# M304B.net
KiCad netlist of a schematic drawn in EAGLE
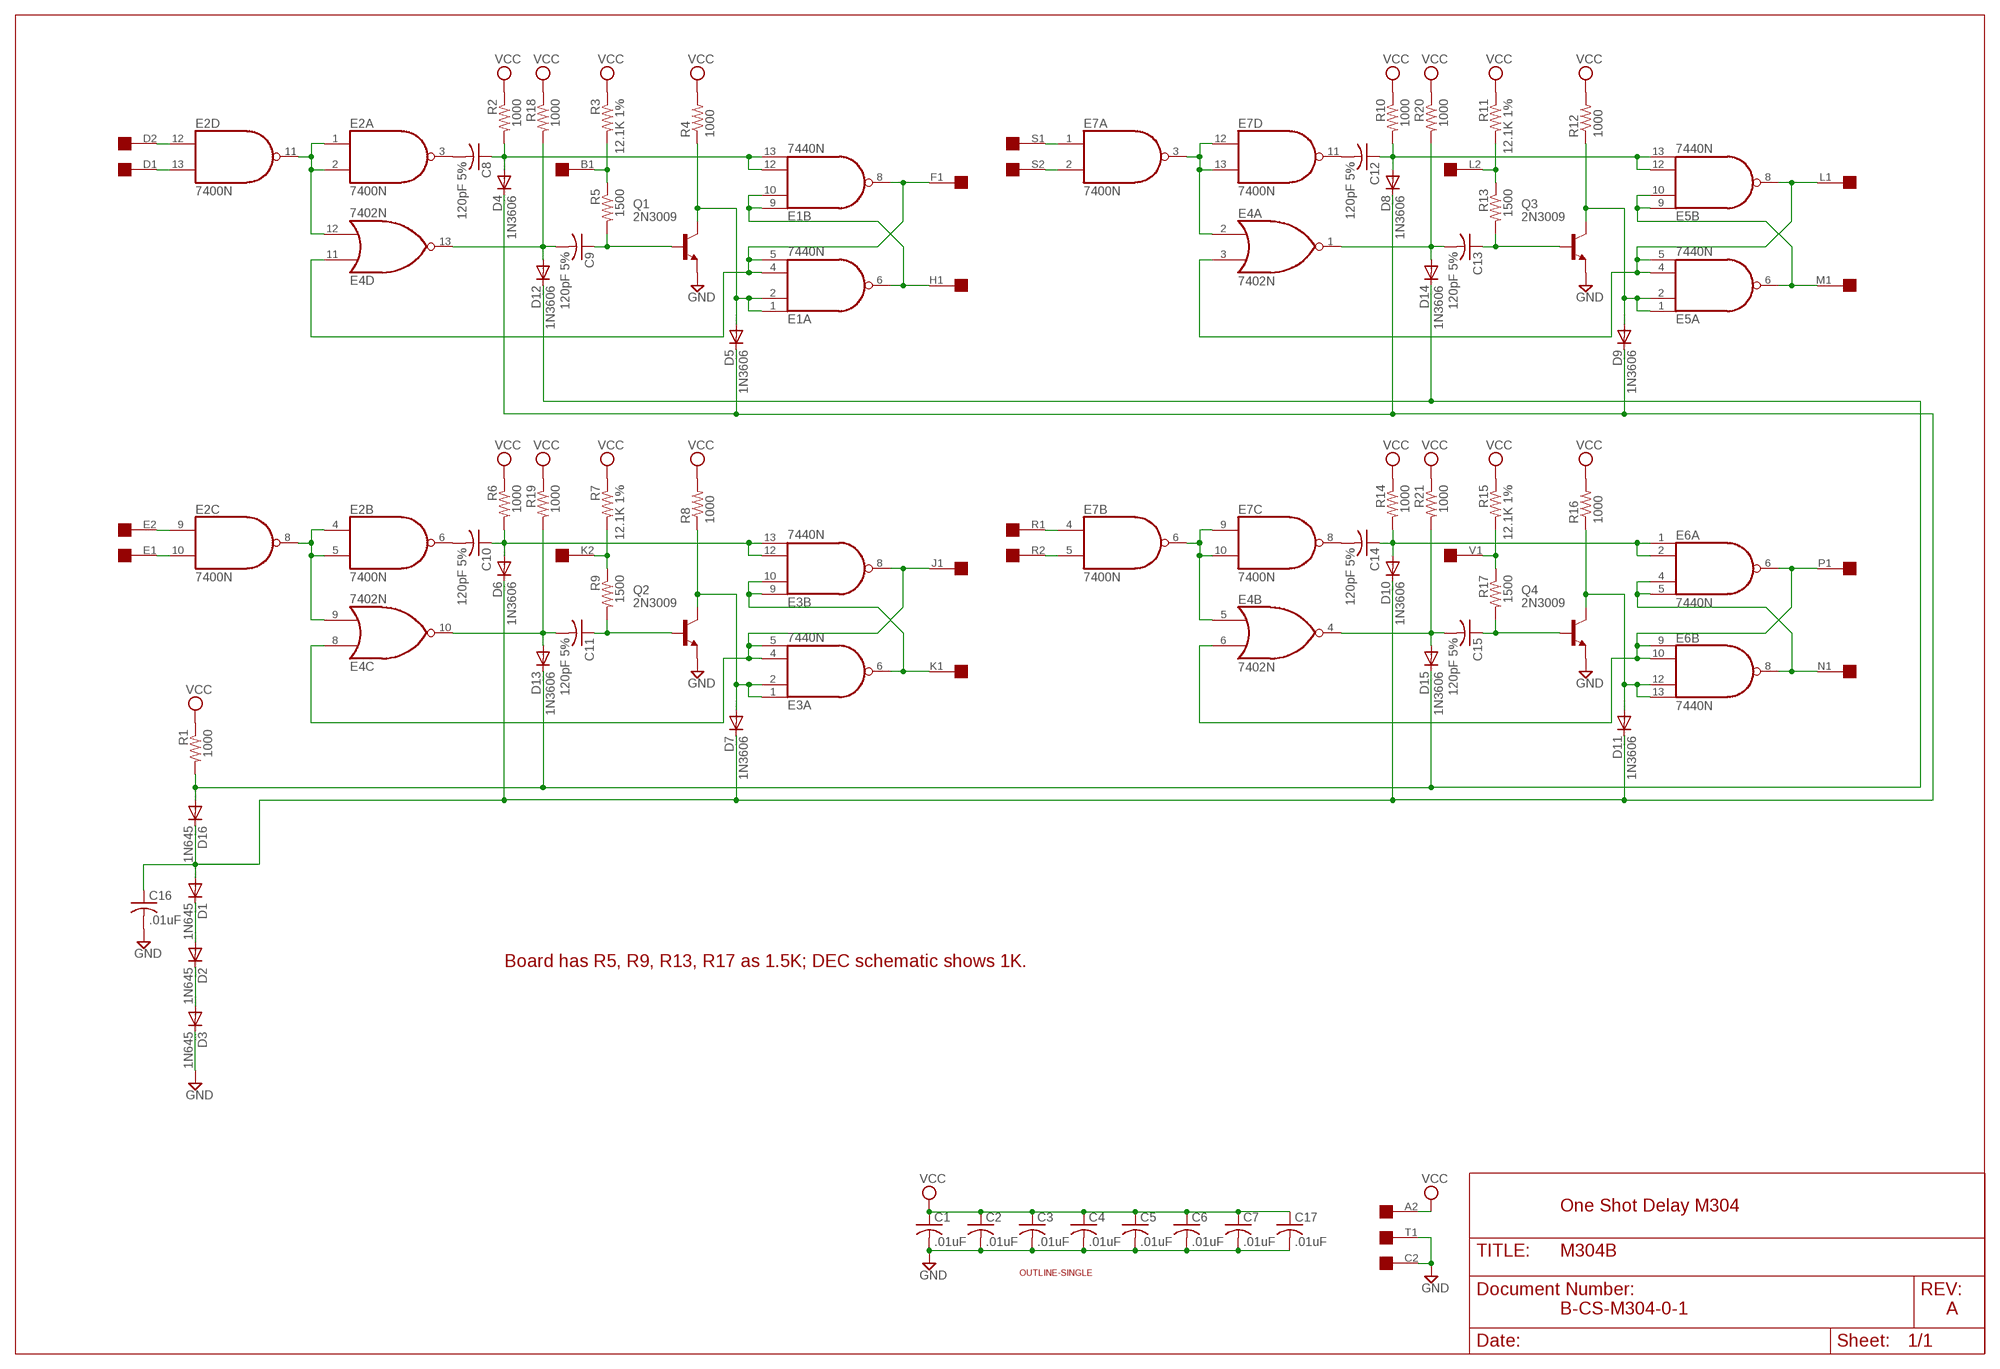
[diagram p0: schematic, sheet 1]

(export (version "E")
  (design (tool "Eeschema 10.0.6"))
  (components
    (comp (ref "C1")
      (value ".01uF")
      (footprint "eagle-import:C050-025X075")
      (libsource (lib "eagle-import") (part "C-US050-025X075"))
    )
    (comp (ref "C2")
      (value ".01uF")
      (footprint "eagle-import:C050-025X075")
      (libsource (lib "eagle-import") (part "C-US050-025X075"))
    )
    (comp (ref "C3")
      (value ".01uF")
      (footprint "eagle-import:C050-025X075")
      (libsource (lib "eagle-import") (part "C-US050-025X075"))
    )
    (comp (ref "C4")
      (value ".01uF")
      (footprint "eagle-import:C050-025X075")
      (libsource (lib "eagle-import") (part "C-US050-025X075"))
    )
    (comp (ref "C5")
      (value ".01uF")
      (footprint "eagle-import:C050-025X075")
      (libsource (lib "eagle-import") (part "C-US050-025X075"))
    )
    (comp (ref "C6")
      (value ".01uF")
      (footprint "eagle-import:C050-025X075")
      (libsource (lib "eagle-import") (part "C-US050-025X075"))
    )
    (comp (ref "C7")
      (value ".01uF")
      (footprint "eagle-import:C050-025X075")
      (libsource (lib "eagle-import") (part "C-US050-025X075"))
    )
    (comp (ref "C8")
      (value "120pF 5%")
      (footprint "eagle-import:C050-025X075")
      (libsource (lib "eagle-import") (part "C-US050-025X075"))
    )
    (comp (ref "C9")
      (value "120pF 5%")
      (footprint "eagle-import:C050-025X075")
      (libsource (lib "eagle-import") (part "C-US050-025X075"))
    )
    (comp (ref "C10")
      (value "120pF 5%")
      (footprint "eagle-import:C050-025X075")
      (libsource (lib "eagle-import") (part "C-US050-025X075"))
    )
    (comp (ref "C11")
      (value "120pF 5%")
      (footprint "eagle-import:C050-025X075")
      (libsource (lib "eagle-import") (part "C-US050-025X075"))
    )
    (comp (ref "C12")
      (value "120pF 5%")
      (footprint "eagle-import:C050-025X075")
      (libsource (lib "eagle-import") (part "C-US050-025X075"))
    )
    (comp (ref "C13")
      (value "120pF 5%")
      (footprint "eagle-import:C050-025X075")
      (libsource (lib "eagle-import") (part "C-US050-025X075"))
    )
    (comp (ref "C14")
      (value "120pF 5%")
      (footprint "eagle-import:C050-025X075")
      (libsource (lib "eagle-import") (part "C-US050-025X075"))
    )
    (comp (ref "C15")
      (value "120pF 5%")
      (footprint "eagle-import:C050-025X075")
      (libsource (lib "eagle-import") (part "C-US050-025X075"))
    )
    (comp (ref "C16")
      (value ".01uF")
      (footprint "eagle-import:C050-025X075")
      (libsource (lib "eagle-import") (part "C-US050-025X075"))
    )
    (comp (ref "C17")
      (value ".01uF")
      (footprint "eagle-import:C050-025X075")
      (libsource (lib "eagle-import") (part "C-US050-025X075"))
    )
    (comp (ref "D1")
      (value "1N645")
      (footprint "eagle-import:DO35-10")
      (libsource (lib "eagle-import") (part "1N4148DO35-10"))
    )
    (comp (ref "D2")
      (value "1N645")
      (footprint "eagle-import:DO35-10")
      (libsource (lib "eagle-import") (part "1N4148DO35-10"))
    )
    (comp (ref "D3")
      (value "1N645")
      (footprint "eagle-import:DO35-10")
      (libsource (lib "eagle-import") (part "1N4148DO35-10"))
    )
    (comp (ref "D4")
      (value "1N3606")
      (footprint "eagle-import:DO35-10")
      (libsource (lib "eagle-import") (part "1N4148DO35-10"))
    )
    (comp (ref "D5")
      (value "1N3606")
      (footprint "eagle-import:DO35-10")
      (libsource (lib "eagle-import") (part "1N4148DO35-10"))
    )
    (comp (ref "D6")
      (value "1N3606")
      (footprint "eagle-import:DO35-10")
      (libsource (lib "eagle-import") (part "1N4148DO35-10"))
    )
    (comp (ref "D7")
      (value "1N3606")
      (footprint "eagle-import:DO35-10")
      (libsource (lib "eagle-import") (part "1N4148DO35-10"))
    )
    (comp (ref "D8")
      (value "1N3606")
      (footprint "eagle-import:DO35-10")
      (libsource (lib "eagle-import") (part "1N4148DO35-10"))
    )
    (comp (ref "D9")
      (value "1N3606")
      (footprint "eagle-import:DO35-10")
      (libsource (lib "eagle-import") (part "1N4148DO35-10"))
    )
    (comp (ref "D10")
      (value "1N3606")
      (footprint "eagle-import:DO35-10")
      (libsource (lib "eagle-import") (part "1N4148DO35-10"))
    )
    (comp (ref "D11")
      (value "1N3606")
      (footprint "eagle-import:DO35-10")
      (libsource (lib "eagle-import") (part "1N4148DO35-10"))
    )
    (comp (ref "D12")
      (value "1N3606")
      (footprint "eagle-import:DO35-10")
      (libsource (lib "eagle-import") (part "1N4148DO35-10"))
    )
    (comp (ref "D13")
      (value "1N3606")
      (footprint "eagle-import:DO35-10")
      (libsource (lib "eagle-import") (part "1N4148DO35-10"))
    )
    (comp (ref "D14")
      (value "1N3606")
      (footprint "eagle-import:DO35-10")
      (libsource (lib "eagle-import") (part "1N4148DO35-10"))
    )
    (comp (ref "D15")
      (value "1N3606")
      (footprint "eagle-import:DO35-10")
      (libsource (lib "eagle-import") (part "1N4148DO35-10"))
    )
    (comp (ref "D16")
      (value "1N645")
      (footprint "eagle-import:DO35-10")
      (libsource (lib "eagle-import") (part "1N4148DO35-10"))
    )
    (comp (ref "E1")
      (value "7440N")
      (footprint "eagle-import:DIL14")
      (libsource (lib "eagle-import") (part "7420NS"))
    )
    (comp (ref "E2")
      (value "7400N")
      (footprint "eagle-import:DIL14")
      (libsource (lib "eagle-import") (part "7400N"))
    )
    (comp (ref "E3")
      (value "7440N")
      (footprint "eagle-import:DIL14")
      (libsource (lib "eagle-import") (part "7420NS"))
    )
    (comp (ref "E4")
      (value "7402N")
      (footprint "eagle-import:DIL14")
      (libsource (lib "eagle-import") (part "7402N"))
    )
    (comp (ref "E5")
      (value "7440N")
      (footprint "eagle-import:DIL14")
      (libsource (lib "eagle-import") (part "7420NS"))
    )
    (comp (ref "E6")
      (value "7440N")
      (footprint "eagle-import:DIL14")
      (libsource (lib "eagle-import") (part "7420NS"))
    )
    (comp (ref "E7")
      (value "7400N")
      (footprint "eagle-import:DIL14")
      (libsource (lib "eagle-import") (part "7400N"))
    )
    (comp (ref "Q1")
      (value "2N3009")
      (footprint "eagle-import:TO39")
      (libsource (lib "eagle-import") (part "-NPN-TO39-EBC2N3019"))
    )
    (comp (ref "Q2")
      (value "2N3009")
      (footprint "eagle-import:TO39")
      (libsource (lib "eagle-import") (part "-NPN-TO39-EBC2N3019"))
    )
    (comp (ref "Q3")
      (value "2N3009")
      (footprint "eagle-import:TO39")
      (libsource (lib "eagle-import") (part "-NPN-TO39-EBC2N3019"))
    )
    (comp (ref "Q4")
      (value "2N3009")
      (footprint "eagle-import:TO39")
      (libsource (lib "eagle-import") (part "-NPN-TO39-EBC2N3019"))
    )
    (comp (ref "R1")
      (value "1000")
      (footprint "eagle-import:0207_10")
      (libsource (lib "eagle-import") (part "R-US_0207/10"))
    )
    (comp (ref "R2")
      (value "1000")
      (footprint "eagle-import:0207_10")
      (libsource (lib "eagle-import") (part "R-US_0207/10"))
    )
    (comp (ref "R3")
      (value "12.1K 1%")
      (footprint "eagle-import:0207_15")
      (libsource (lib "eagle-import") (part "R-US_0207/15"))
    )
    (comp (ref "R4")
      (value "1000")
      (footprint "eagle-import:0207_10")
      (libsource (lib "eagle-import") (part "R-US_0207/10"))
    )
    (comp (ref "R5")
      (value "1500")
      (footprint "eagle-import:0207_10")
      (libsource (lib "eagle-import") (part "R-US_0207/10"))
    )
    (comp (ref "R6")
      (value "1000")
      (footprint "eagle-import:0207_10")
      (libsource (lib "eagle-import") (part "R-US_0207/10"))
    )
    (comp (ref "R7")
      (value "12.1K 1%")
      (footprint "eagle-import:0207_15")
      (libsource (lib "eagle-import") (part "R-US_0207/15"))
    )
    (comp (ref "R8")
      (value "1000")
      (footprint "eagle-import:0207_10")
      (libsource (lib "eagle-import") (part "R-US_0207/10"))
    )
    (comp (ref "R9")
      (value "1500")
      (footprint "eagle-import:0207_10")
      (libsource (lib "eagle-import") (part "R-US_0207/10"))
    )
    (comp (ref "R10")
      (value "1000")
      (footprint "eagle-import:0207_10")
      (libsource (lib "eagle-import") (part "R-US_0207/10"))
    )
    (comp (ref "R11")
      (value "12.1K 1%")
      (footprint "eagle-import:0207_15")
      (libsource (lib "eagle-import") (part "R-US_0207/15"))
    )
    (comp (ref "R12")
      (value "1000")
      (footprint "eagle-import:0207_10")
      (libsource (lib "eagle-import") (part "R-US_0207/10"))
    )
    (comp (ref "R13")
      (value "1500")
      (footprint "eagle-import:0207_10")
      (libsource (lib "eagle-import") (part "R-US_0207/10"))
    )
    (comp (ref "R14")
      (value "1000")
      (footprint "eagle-import:0207_10")
      (libsource (lib "eagle-import") (part "R-US_0207/10"))
    )
    (comp (ref "R15")
      (value "12.1K 1%")
      (footprint "eagle-import:0207_15")
      (libsource (lib "eagle-import") (part "R-US_0207/15"))
    )
    (comp (ref "R16")
      (value "1000")
      (footprint "eagle-import:0207_10")
      (libsource (lib "eagle-import") (part "R-US_0207/10"))
    )
    (comp (ref "R17")
      (value "1500")
      (footprint "eagle-import:0207_10")
      (libsource (lib "eagle-import") (part "R-US_0207/10"))
    )
    (comp (ref "R18")
      (value "1000")
      (footprint "eagle-import:0207_10")
      (libsource (lib "eagle-import") (part "R-US_0207/10"))
    )
    (comp (ref "R19")
      (value "1000")
      (footprint "eagle-import:0207_10")
      (libsource (lib "eagle-import") (part "R-US_0207/10"))
    )
    (comp (ref "R20")
      (value "1000")
      (footprint "eagle-import:0207_10")
      (libsource (lib "eagle-import") (part "R-US_0207/10"))
    )
    (comp (ref "R21")
      (value "1000")
      (footprint "eagle-import:0207_10")
      (libsource (lib "eagle-import") (part "R-US_0207/10"))
    )
    (comp (ref "U$1")
      (value "SINGLE")
      (footprint "eagle-import:EDGE-CON2")
      (libsource (lib "eagle-import") (part "SINGLE"))
    )
    (comp (ref "U$2")
      (value "OUTLINE-SINGLE")
      (footprint "eagle-import:SINGLE")
      (libsource (lib "eagle-import") (part "OUTLINE-SINGLE"))
    )
  )
  (nets
    (net (code "1") (name "GND") (class "Default")
      (node (ref "C1") (pin "2") (pinfunction "2_2") (pintype "passive"))
      (node (ref "C16") (pin "2") (pinfunction "2_2") (pintype "passive"))
      (node (ref "C17") (pin "2") (pinfunction "2_2") (pintype "passive"))
      (node (ref "C2") (pin "2") (pinfunction "2_2") (pintype "passive"))
      (node (ref "C3") (pin "2") (pinfunction "2_2") (pintype "passive"))
      (node (ref "C4") (pin "2") (pinfunction "2_2") (pintype "passive"))
      (node (ref "C5") (pin "2") (pinfunction "2_2") (pintype "passive"))
      (node (ref "C6") (pin "2") (pinfunction "2_2") (pintype "passive"))
      (node (ref "C7") (pin "2") (pinfunction "2_2") (pintype "passive"))
      (node (ref "D3") (pin "C") (pinfunction "C_C") (pintype "passive"))
      (node (ref "Q1") (pin "1") (pinfunction "E_1") (pintype "passive"))
      (node (ref "Q2") (pin "1") (pinfunction "E_1") (pintype "passive"))
      (node (ref "Q3") (pin "1") (pinfunction "E_1") (pintype "passive"))
      (node (ref "Q4") (pin "1") (pinfunction "E_1") (pintype "passive"))
      (node (ref "U$1") (pin "C2") (pinfunction "1_C2") (pintype "bidirectional"))
      (node (ref "U$1") (pin "T1") (pinfunction "1_T1") (pintype "bidirectional"))
    )
    (net (code "2") (name "Net-(C16-Pad1)") (class "Default")
      (node (ref "C16") (pin "1") (pinfunction "1_1") (pintype "passive"))
      (node (ref "D1") (pin "A") (pinfunction "A_A") (pintype "passive"))
      (node (ref "D10") (pin "C") (pinfunction "C_C") (pintype "passive"))
      (node (ref "D11") (pin "C") (pinfunction "C_C") (pintype "passive"))
      (node (ref "D16") (pin "C") (pinfunction "C_C") (pintype "passive"))
      (node (ref "D4") (pin "C") (pinfunction "C_C") (pintype "passive"))
      (node (ref "D5") (pin "C") (pinfunction "C_C") (pintype "passive"))
      (node (ref "D6") (pin "C") (pinfunction "C_C") (pintype "passive"))
      (node (ref "D7") (pin "C") (pinfunction "C_C") (pintype "passive"))
      (node (ref "D8") (pin "C") (pinfunction "C_C") (pintype "passive"))
      (node (ref "D9") (pin "C") (pinfunction "C_C") (pintype "passive"))
    )
    (net (code "3") (name "Net-(D1-PadC)") (class "Default")
      (node (ref "D1") (pin "C") (pinfunction "C_C") (pintype "passive"))
      (node (ref "D2") (pin "A") (pinfunction "A_A") (pintype "passive"))
    )
    (net (code "4") (name "Net-(D2-PadC)") (class "Default")
      (node (ref "D2") (pin "C") (pinfunction "C_C") (pintype "passive"))
      (node (ref "D3") (pin "A") (pinfunction "A_A") (pintype "passive"))
    )
    (net (code "5") (name "Net-(D12-PadC)") (class "Default")
      (node (ref "D12") (pin "C") (pinfunction "C_C") (pintype "passive"))
      (node (ref "D13") (pin "C") (pinfunction "C_C") (pintype "passive"))
      (node (ref "D14") (pin "C") (pinfunction "C_C") (pintype "passive"))
      (node (ref "D15") (pin "C") (pinfunction "C_C") (pintype "passive"))
      (node (ref "D16") (pin "A") (pinfunction "A_A") (pintype "passive"))
      (node (ref "R1") (pin "2") (pinfunction "2_2") (pintype "passive"))
    )
    (net (code "6") (name "Net-(E1A-I0)") (class "Default")
      (node (ref "D5") (pin "A") (pinfunction "A_A") (pintype "passive"))
      (node (ref "E1") (pin "1") (pinfunction "I0_1") (pintype "input"))
      (node (ref "E1") (pin "2") (pinfunction "I1_2") (pintype "input"))
      (node (ref "Q1") (pin "3") (pinfunction "C_3") (pintype "passive"))
      (node (ref "R4") (pin "1") (pinfunction "1_1") (pintype "passive"))
    )
    (net (code "7") (name "Net-(E1A-I2)") (class "Default")
      (node (ref "E1") (pin "4") (pinfunction "I2_4") (pintype "input"))
      (node (ref "E1") (pin "5") (pinfunction "I3_5") (pintype "input"))
      (node (ref "E1") (pin "8") (pinfunction "O_8") (pintype "output"))
      (node (ref "E4") (pin "11") (pinfunction "I0_11") (pintype "input"))
      (node (ref "U$1") (pin "F1") (pinfunction "1_F1") (pintype "bidirectional"))
    )
    (net (code "8") (name "Net-(E1A-O)") (class "Default")
      (node (ref "E1") (pin "10") (pinfunction "I1_10") (pintype "input"))
      (node (ref "E1") (pin "6") (pinfunction "O_6") (pintype "output"))
      (node (ref "E1") (pin "9") (pinfunction "I0_9") (pintype "input"))
      (node (ref "U$1") (pin "H1") (pinfunction "1_H1") (pintype "bidirectional"))
    )
    (net (code "9") (name "Net-(E1B-I2)") (class "Default")
      (node (ref "C8") (pin "1") (pinfunction "1_1") (pintype "passive"))
      (node (ref "D4") (pin "A") (pinfunction "A_A") (pintype "passive"))
      (node (ref "E1") (pin "12") (pinfunction "I2_12") (pintype "input"))
      (node (ref "E1") (pin "13") (pinfunction "I3_13") (pintype "input"))
      (node (ref "R2") (pin "2") (pinfunction "2_2") (pintype "passive"))
    )
    (net (code "10") (name "Net-(E2A-I0)") (class "Default")
      (node (ref "E2") (pin "1") (pinfunction "I0_1") (pintype "input"))
      (node (ref "E2") (pin "11") (pinfunction "O_11") (pintype "output"))
      (node (ref "E2") (pin "2") (pinfunction "I1_2") (pintype "input"))
      (node (ref "E4") (pin "12") (pinfunction "I1_12") (pintype "input"))
    )
    (net (code "11") (name "Net-(E2A-O)") (class "Default")
      (node (ref "C8") (pin "2") (pinfunction "2_2") (pintype "passive"))
      (node (ref "E2") (pin "3") (pinfunction "O_3") (pintype "output"))
    )
    (net (code "12") (name "Net-(E2B-I0)") (class "Default")
      (node (ref "E2") (pin "4") (pinfunction "I0_4") (pintype "input"))
      (node (ref "E2") (pin "5") (pinfunction "I1_5") (pintype "input"))
      (node (ref "E2") (pin "8") (pinfunction "O_8") (pintype "output"))
      (node (ref "E4") (pin "9") (pinfunction "I1_9") (pintype "input"))
    )
    (net (code "13") (name "Net-(E2B-O)") (class "Default")
      (node (ref "C10") (pin "2") (pinfunction "2_2") (pintype "passive"))
      (node (ref "E2") (pin "6") (pinfunction "O_6") (pintype "output"))
    )
    (net (code "14") (name "Net-(E2C-I0)") (class "Default")
      (node (ref "E2") (pin "9") (pinfunction "I0_9") (pintype "input"))
      (node (ref "U$1") (pin "E2") (pinfunction "1_E2") (pintype "bidirectional"))
    )
    (net (code "15") (name "Net-(E2C-I1)") (class "Default")
      (node (ref "E2") (pin "10") (pinfunction "I1_10") (pintype "input"))
      (node (ref "U$1") (pin "E1") (pinfunction "1_E1") (pintype "bidirectional"))
    )
    (net (code "16") (name "Net-(E2D-I0)") (class "Default")
      (node (ref "E2") (pin "12") (pinfunction "I0_12") (pintype "input"))
      (node (ref "U$1") (pin "D2") (pinfunction "1_D2") (pintype "bidirectional"))
    )
    (net (code "17") (name "Net-(E2D-I1)") (class "Default")
      (node (ref "E2") (pin "13") (pinfunction "I1_13") (pintype "input"))
      (node (ref "U$1") (pin "D1") (pinfunction "1_D1") (pintype "bidirectional"))
    )
    (net (code "18") (name "Net-(E3A-I0)") (class "Default")
      (node (ref "D7") (pin "A") (pinfunction "A_A") (pintype "passive"))
      (node (ref "E3") (pin "1") (pinfunction "I0_1") (pintype "input"))
      (node (ref "E3") (pin "2") (pinfunction "I1_2") (pintype "input"))
      (node (ref "Q2") (pin "3") (pinfunction "C_3") (pintype "passive"))
      (node (ref "R8") (pin "1") (pinfunction "1_1") (pintype "passive"))
    )
    (net (code "19") (name "Net-(E3A-I2)") (class "Default")
      (node (ref "E3") (pin "4") (pinfunction "I2_4") (pintype "input"))
      (node (ref "E3") (pin "5") (pinfunction "I3_5") (pintype "input"))
      (node (ref "E3") (pin "8") (pinfunction "O_8") (pintype "output"))
      (node (ref "E4") (pin "8") (pinfunction "I0_8") (pintype "input"))
      (node (ref "U$1") (pin "J1") (pinfunction "1_J1") (pintype "bidirectional"))
    )
    (net (code "20") (name "Net-(E3A-O)") (class "Default")
      (node (ref "E3") (pin "10") (pinfunction "I1_10") (pintype "input"))
      (node (ref "E3") (pin "6") (pinfunction "O_6") (pintype "output"))
      (node (ref "E3") (pin "9") (pinfunction "I0_9") (pintype "input"))
      (node (ref "U$1") (pin "K1") (pinfunction "1_K1") (pintype "bidirectional"))
    )
    (net (code "21") (name "Net-(E3B-I2)") (class "Default")
      (node (ref "C10") (pin "1") (pinfunction "1_1") (pintype "passive"))
      (node (ref "D6") (pin "A") (pinfunction "A_A") (pintype "passive"))
      (node (ref "E3") (pin "12") (pinfunction "I2_12") (pintype "input"))
      (node (ref "E3") (pin "13") (pinfunction "I3_13") (pintype "input"))
      (node (ref "R6") (pin "2") (pinfunction "2_2") (pintype "passive"))
    )
    (net (code "22") (name "Net-(E4A-I0)") (class "Default")
      (node (ref "E4") (pin "2") (pinfunction "I0_2") (pintype "input"))
      (node (ref "E7") (pin "12") (pinfunction "I0_12") (pintype "input"))
      (node (ref "E7") (pin "13") (pinfunction "I1_13") (pintype "input"))
      (node (ref "E7") (pin "3") (pinfunction "O_3") (pintype "output"))
    )
    (net (code "23") (name "Net-(E4A-I1)") (class "Default")
      (node (ref "E4") (pin "3") (pinfunction "I1_3") (pintype "input"))
      (node (ref "E5") (pin "4") (pinfunction "I2_4") (pintype "input"))
      (node (ref "E5") (pin "5") (pinfunction "I3_5") (pintype "input"))
      (node (ref "E5") (pin "8") (pinfunction "O_8") (pintype "output"))
      (node (ref "U$1") (pin "L1") (pinfunction "1_L1") (pintype "bidirectional"))
    )
    (net (code "24") (name "Net-(E4A-O)") (class "Default")
      (node (ref "C13") (pin "2") (pinfunction "2_2") (pintype "passive"))
      (node (ref "D14") (pin "A") (pinfunction "A_A") (pintype "passive"))
      (node (ref "E4") (pin "1") (pinfunction "O_1") (pintype "output"))
      (node (ref "R20") (pin "2") (pinfunction "2_2") (pintype "passive"))
    )
    (net (code "25") (name "Net-(E4B-I0)") (class "Default")
      (node (ref "E4") (pin "5") (pinfunction "I0_5") (pintype "input"))
      (node (ref "E7") (pin "10") (pinfunction "I1_10") (pintype "input"))
      (node (ref "E7") (pin "6") (pinfunction "O_6") (pintype "output"))
      (node (ref "E7") (pin "9") (pinfunction "I0_9") (pintype "input"))
    )
    (net (code "26") (name "Net-(E4B-I1)") (class "Default")
      (node (ref "E4") (pin "6") (pinfunction "I1_6") (pintype "input"))
      (node (ref "E6") (pin "10") (pinfunction "I1_10") (pintype "input"))
      (node (ref "E6") (pin "6") (pinfunction "O_6") (pintype "output"))
      (node (ref "E6") (pin "9") (pinfunction "I0_9") (pintype "input"))
      (node (ref "U$1") (pin "P1") (pinfunction "1_P1") (pintype "bidirectional"))
    )
    (net (code "27") (name "Net-(E4B-O)") (class "Default")
      (node (ref "C15") (pin "2") (pinfunction "2_2") (pintype "passive"))
      (node (ref "D15") (pin "A") (pinfunction "A_A") (pintype "passive"))
      (node (ref "E4") (pin "4") (pinfunction "O_4") (pintype "output"))
      (node (ref "R21") (pin "2") (pinfunction "2_2") (pintype "passive"))
    )
    (net (code "28") (name "Net-(E4C-O)") (class "Default")
      (node (ref "C11") (pin "2") (pinfunction "2_2") (pintype "passive"))
      (node (ref "D13") (pin "A") (pinfunction "A_A") (pintype "passive"))
      (node (ref "E4") (pin "10") (pinfunction "O_10") (pintype "output"))
      (node (ref "R19") (pin "2") (pinfunction "2_2") (pintype "passive"))
    )
    (net (code "29") (name "Net-(E4D-O)") (class "Default")
      (node (ref "C9") (pin "2") (pinfunction "2_2") (pintype "passive"))
      (node (ref "D12") (pin "A") (pinfunction "A_A") (pintype "passive"))
      (node (ref "E4") (pin "13") (pinfunction "O_13") (pintype "output"))
      (node (ref "R18") (pin "2") (pinfunction "2_2") (pintype "passive"))
    )
    (net (code "30") (name "Net-(E5A-I0)") (class "Default")
      (node (ref "D9") (pin "A") (pinfunction "A_A") (pintype "passive"))
      (node (ref "E5") (pin "1") (pinfunction "I0_1") (pintype "input"))
      (node (ref "E5") (pin "2") (pinfunction "I1_2") (pintype "input"))
      (node (ref "Q3") (pin "3") (pinfunction "C_3") (pintype "passive"))
      (node (ref "R12") (pin "1") (pinfunction "1_1") (pintype "passive"))
    )
    (net (code "31") (name "Net-(E5A-O)") (class "Default")
      (node (ref "E5") (pin "10") (pinfunction "I1_10") (pintype "input"))
      (node (ref "E5") (pin "6") (pinfunction "O_6") (pintype "output"))
      (node (ref "E5") (pin "9") (pinfunction "I0_9") (pintype "input"))
      (node (ref "U$1") (pin "M1") (pinfunction "1_M1") (pintype "bidirectional"))
    )
    (net (code "32") (name "Net-(E5B-I2)") (class "Default")
      (node (ref "C12") (pin "1") (pinfunction "1_1") (pintype "passive"))
      (node (ref "D8") (pin "A") (pinfunction "A_A") (pintype "passive"))
      (node (ref "E5") (pin "12") (pinfunction "I2_12") (pintype "input"))
      (node (ref "E5") (pin "13") (pinfunction "I3_13") (pintype "input"))
      (node (ref "R10") (pin "2") (pinfunction "2_2") (pintype "passive"))
    )
    (net (code "33") (name "Net-(E6A-I0)") (class "Default")
      (node (ref "C14") (pin "1") (pinfunction "1_1") (pintype "passive"))
      (node (ref "D10") (pin "A") (pinfunction "A_A") (pintype "passive"))
      (node (ref "E6") (pin "1") (pinfunction "I0_1") (pintype "input"))
      (node (ref "E6") (pin "2") (pinfunction "I1_2") (pintype "input"))
      (node (ref "R14") (pin "2") (pinfunction "2_2") (pintype "passive"))
    )
    (net (code "34") (name "Net-(E6A-I2)") (class "Default")
      (node (ref "E6") (pin "4") (pinfunction "I2_4") (pintype "input"))
      (node (ref "E6") (pin "5") (pinfunction "I3_5") (pintype "input"))
      (node (ref "E6") (pin "8") (pinfunction "O_8") (pintype "output"))
      (node (ref "U$1") (pin "N1") (pinfunction "1_N1") (pintype "bidirectional"))
    )
    (net (code "35") (name "Net-(E6B-I2)") (class "Default")
      (node (ref "D11") (pin "A") (pinfunction "A_A") (pintype "passive"))
      (node (ref "E6") (pin "12") (pinfunction "I2_12") (pintype "input"))
      (node (ref "E6") (pin "13") (pinfunction "I3_13") (pintype "input"))
      (node (ref "Q4") (pin "3") (pinfunction "C_3") (pintype "passive"))
      (node (ref "R16") (pin "1") (pinfunction "1_1") (pintype "passive"))
    )
    (net (code "36") (name "Net-(E7A-I0)") (class "Default")
      (node (ref "E7") (pin "1") (pinfunction "I0_1") (pintype "input"))
      (node (ref "U$1") (pin "S1") (pinfunction "1_S1") (pintype "bidirectional"))
    )
    (net (code "37") (name "Net-(E7A-I1)") (class "Default")
      (node (ref "E7") (pin "2") (pinfunction "I1_2") (pintype "input"))
      (node (ref "U$1") (pin "S2") (pinfunction "1_S2") (pintype "bidirectional"))
    )
    (net (code "38") (name "Net-(E7B-I0)") (class "Default")
      (node (ref "E7") (pin "4") (pinfunction "I0_4") (pintype "input"))
      (node (ref "U$1") (pin "R1") (pinfunction "1_R1") (pintype "bidirectional"))
    )
    (net (code "39") (name "Net-(E7B-I1)") (class "Default")
      (node (ref "E7") (pin "5") (pinfunction "I1_5") (pintype "input"))
      (node (ref "U$1") (pin "R2") (pinfunction "1_R2") (pintype "bidirectional"))
    )
    (net (code "40") (name "Net-(E7C-O)") (class "Default")
      (node (ref "C14") (pin "2") (pinfunction "2_2") (pintype "passive"))
      (node (ref "E7") (pin "8") (pinfunction "O_8") (pintype "output"))
    )
    (net (code "41") (name "Net-(E7D-O)") (class "Default")
      (node (ref "C12") (pin "2") (pinfunction "2_2") (pintype "passive"))
      (node (ref "E7") (pin "11") (pinfunction "O_11") (pintype "output"))
    )
    (net (code "42") (name "Net-(Q1-B)") (class "Default")
      (node (ref "C9") (pin "1") (pinfunction "1_1") (pintype "passive"))
      (node (ref "Q1") (pin "2") (pinfunction "B_2") (pintype "passive"))
      (node (ref "R5") (pin "2") (pinfunction "2_2") (pintype "passive"))
    )
    (net (code "43") (name "Net-(Q2-B)") (class "Default")
      (node (ref "C11") (pin "1") (pinfunction "1_1") (pintype "passive"))
      (node (ref "Q2") (pin "2") (pinfunction "B_2") (pintype "passive"))
      (node (ref "R9") (pin "2") (pinfunction "2_2") (pintype "passive"))
    )
    (net (code "44") (name "Net-(Q3-B)") (class "Default")
      (node (ref "C13") (pin "1") (pinfunction "1_1") (pintype "passive"))
      (node (ref "Q3") (pin "2") (pinfunction "B_2") (pintype "passive"))
      (node (ref "R13") (pin "2") (pinfunction "2_2") (pintype "passive"))
    )
    (net (code "45") (name "Net-(Q4-B)") (class "Default")
      (node (ref "C15") (pin "1") (pinfunction "1_1") (pintype "passive"))
      (node (ref "Q4") (pin "2") (pinfunction "B_2") (pintype "passive"))
      (node (ref "R17") (pin "2") (pinfunction "2_2") (pintype "passive"))
    )
    (net (code "46") (name "Net-(U$1AI-1)") (class "Default")
      (node (ref "R15") (pin "2") (pinfunction "2_2") (pintype "passive"))
      (node (ref "R17") (pin "1") (pinfunction "1_1") (pintype "passive"))
      (node (ref "U$1") (pin "V1") (pinfunction "1_V1") (pintype "bidirectional"))
    )
    (net (code "47") (name "Net-(U$1C-1)") (class "Default")
      (node (ref "R3") (pin "2") (pinfunction "2_2") (pintype "passive"))
      (node (ref "R5") (pin "1") (pinfunction "1_1") (pintype "passive"))
      (node (ref "U$1") (pin "B1") (pinfunction "1_B1") (pintype "bidirectional"))
    )
    (net (code "48") (name "Net-(U$1R-1)") (class "Default")
      (node (ref "R7") (pin "2") (pinfunction "2_2") (pintype "passive"))
      (node (ref "R9") (pin "1") (pinfunction "1_1") (pintype "passive"))
      (node (ref "U$1") (pin "K2") (pinfunction "1_K2") (pintype "bidirectional"))
    )
    (net (code "49") (name "Net-(U$1T-1)") (class "Default")
      (node (ref "R11") (pin "2") (pinfunction "2_2") (pintype "passive"))
      (node (ref "R13") (pin "1") (pinfunction "1_1") (pintype "passive"))
      (node (ref "U$1") (pin "L2") (pinfunction "1_L2") (pintype "bidirectional"))
    )
    (net (code "50") (name "VCC") (class "Default")
      (node (ref "C1") (pin "1") (pinfunction "1_1") (pintype "passive"))
      (node (ref "C17") (pin "1") (pinfunction "1_1") (pintype "passive"))
      (node (ref "C2") (pin "1") (pinfunction "1_1") (pintype "passive"))
      (node (ref "C3") (pin "1") (pinfunction "1_1") (pintype "passive"))
      (node (ref "C4") (pin "1") (pinfunction "1_1") (pintype "passive"))
      (node (ref "C5") (pin "1") (pinfunction "1_1") (pintype "passive"))
      (node (ref "C6") (pin "1") (pinfunction "1_1") (pintype "passive"))
      (node (ref "C7") (pin "1") (pinfunction "1_1") (pintype "passive"))
      (node (ref "R1") (pin "1") (pinfunction "1_1") (pintype "passive"))
      (node (ref "R10") (pin "1") (pinfunction "1_1") (pintype "passive"))
      (node (ref "R11") (pin "1") (pinfunction "1_1") (pintype "passive"))
      (node (ref "R12") (pin "2") (pinfunction "2_2") (pintype "passive"))
      (node (ref "R14") (pin "1") (pinfunction "1_1") (pintype "passive"))
      (node (ref "R15") (pin "1") (pinfunction "1_1") (pintype "passive"))
      (node (ref "R16") (pin "2") (pinfunction "2_2") (pintype "passive"))
      (node (ref "R18") (pin "1") (pinfunction "1_1") (pintype "passive"))
      (node (ref "R19") (pin "1") (pinfunction "1_1") (pintype "passive"))
      (node (ref "R2") (pin "1") (pinfunction "1_1") (pintype "passive"))
      (node (ref "R20") (pin "1") (pinfunction "1_1") (pintype "passive"))
      (node (ref "R21") (pin "1") (pinfunction "1_1") (pintype "passive"))
      (node (ref "R3") (pin "1") (pinfunction "1_1") (pintype "passive"))
      (node (ref "R4") (pin "2") (pinfunction "2_2") (pintype "passive"))
      (node (ref "R6") (pin "1") (pinfunction "1_1") (pintype "passive"))
      (node (ref "R7") (pin "1") (pinfunction "1_1") (pintype "passive"))
      (node (ref "R8") (pin "2") (pinfunction "2_2") (pintype "passive"))
      (node (ref "U$1") (pin "A2") (pinfunction "1_A2") (pintype "bidirectional"))
    )
  )
)
